# H3_CPU_01.net
KiCad netlist of a schematic drawn in Altium Designer
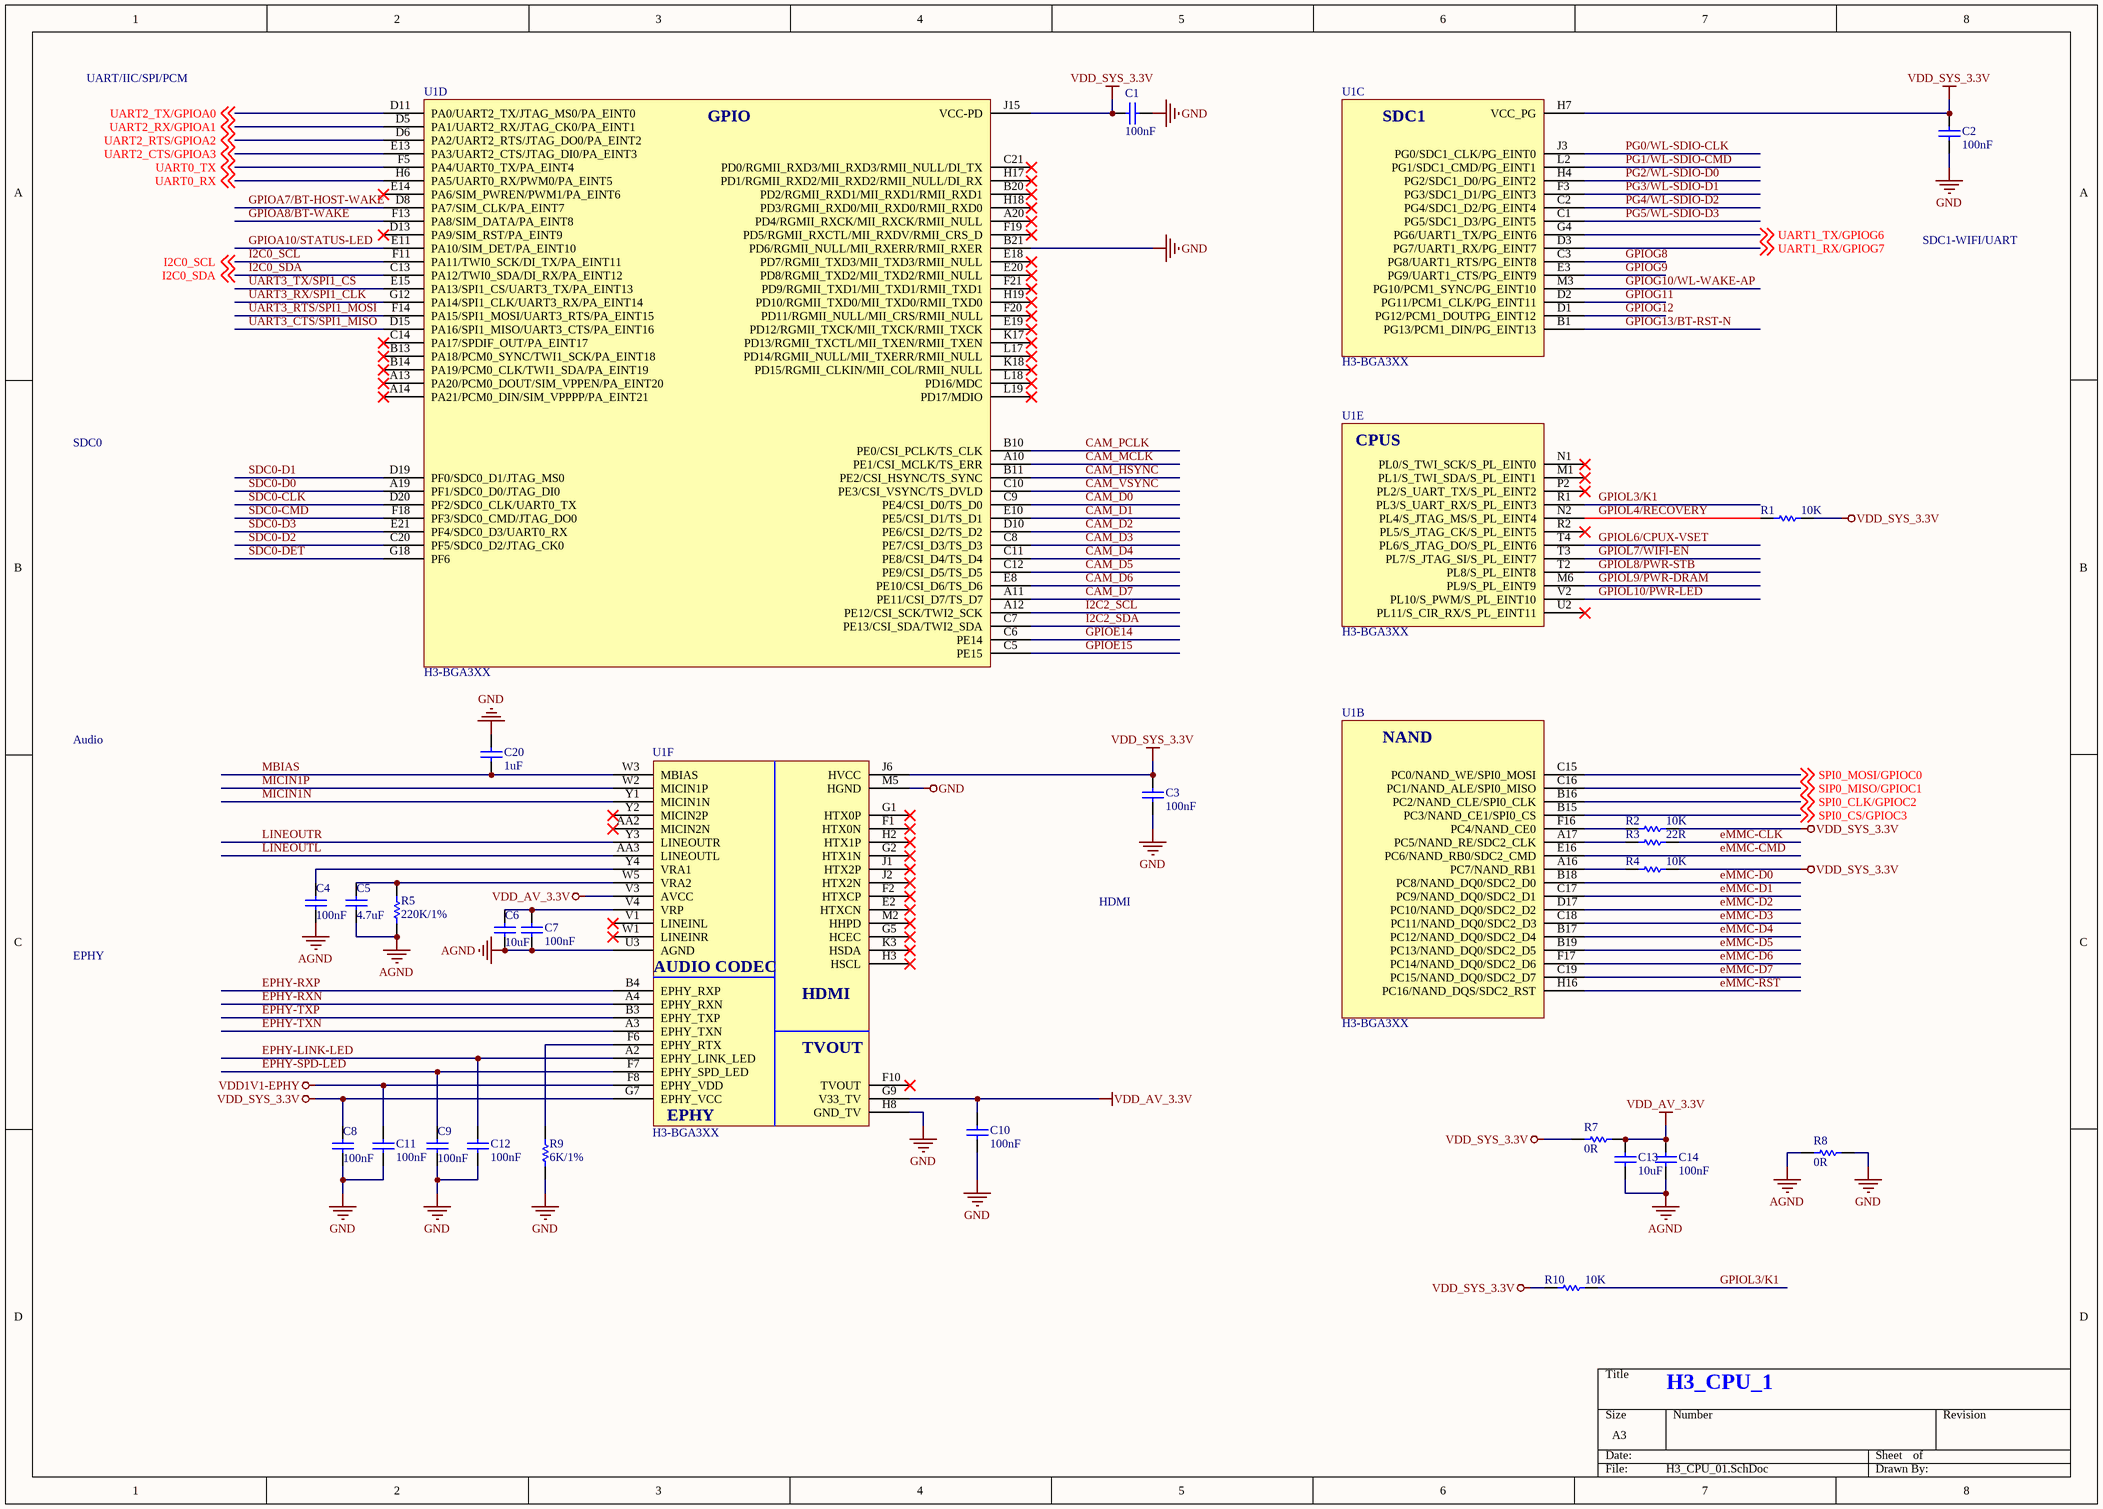
[diagram p0: H3_CPU_01.SchDoc]

(export (version "E")
  (design (tool "Eeschema 10.0.6"))
  (components
    (comp (ref "C1")
      (value "100nF")
      (footprint "H3_Core:C0402")
      (description "电容")
      (fields (field (name "PUBLISHER") "Altium Limited"))
      (libsource (lib "Devices") (part "C0402"))
    )
    (comp (ref "C2")
      (value "100nF")
      (footprint "H3_Core:C0402")
      (description "电容")
      (fields (field (name "PUBLISHER") "Altium Limited"))
      (libsource (lib "Devices") (part "C0402"))
    )
    (comp (ref "C3")
      (value "100nF")
      (footprint "H3_Core:C0402")
      (description "电容")
      (fields (field (name "PUBLISHER") "Altium Limited"))
      (libsource (lib "Devices") (part "C0402"))
    )
    (comp (ref "C4")
      (value "100nF")
      (footprint "H3_Core:C0402")
      (description "电容")
      (fields (field (name "PUBLISHER") "Altium Limited"))
      (libsource (lib "Devices") (part "C0402"))
    )
    (comp (ref "C5")
      (value "4.7uF")
      (footprint "H3_Core:C0402")
      (description "电容")
      (fields (field (name "PUBLISHER") "Altium Limited"))
      (libsource (lib "Devices") (part "C0402"))
    )
    (comp (ref "C6")
      (value "10uF")
      (footprint "H3_Core:C0603")
      (description "电容")
      (fields (field (name "PUBLISHER") "Altium Limited"))
      (libsource (lib "Devices") (part "C0603"))
    )
    (comp (ref "C7")
      (value "100nF")
      (footprint "H3_Core:C0402")
      (description "电容")
      (fields (field (name "PUBLISHER") "Altium Limited"))
      (libsource (lib "Devices") (part "C0402"))
    )
    (comp (ref "C8")
      (value "100nF")
      (footprint "H3_Core:C0402")
      (description "电容")
      (fields (field (name "PUBLISHER") "Altium Limited"))
      (libsource (lib "Devices") (part "C0402"))
    )
    (comp (ref "C9")
      (value "100nF")
      (footprint "H3_Core:C0402")
      (description "电容")
      (fields (field (name "PUBLISHER") "Altium Limited"))
      (libsource (lib "Devices") (part "C0402"))
    )
    (comp (ref "C10")
      (value "100nF")
      (footprint "H3_Core:C0402")
      (description "电容")
      (fields (field (name "PUBLISHER") "Altium Limited"))
      (libsource (lib "Devices") (part "C0402"))
    )
    (comp (ref "C11")
      (value "100nF")
      (footprint "H3_Core:C0402")
      (description "电容")
      (fields (field (name "PUBLISHER") "Altium Limited"))
      (libsource (lib "Devices") (part "C0402"))
    )
    (comp (ref "C12")
      (value "100nF")
      (footprint "H3_Core:C0402")
      (description "电容")
      (fields (field (name "PUBLISHER") "Altium Limited"))
      (libsource (lib "Devices") (part "C0402"))
    )
    (comp (ref "C13")
      (value "10uF")
      (footprint "H3_Core:C0603")
      (description "电容")
      (fields (field (name "PUBLISHER") "Altium Limited"))
      (libsource (lib "Devices") (part "C0603"))
    )
    (comp (ref "C14")
      (value "100nF")
      (footprint "H3_Core:C0402")
      (description "电容")
      (fields (field (name "PUBLISHER") "Altium Limited"))
      (libsource (lib "Devices") (part "C0402"))
    )
    (comp (ref "C20")
      (value "1uF")
      (footprint "H3_Core:C0402")
      (description "电容")
      (fields (field (name "PUBLISHER") "Altium Limited"))
      (libsource (lib "Devices") (part "C0402"))
    )
    (comp (ref "R1")
      (value "10K")
      (footprint "H3_Core:R0402")
      (description "电阻")
      (fields (field (name "PUBLISHER") "Altium Limited"))
      (libsource (lib "Devices") (part "RES0402"))
    )
    (comp (ref "R2")
      (value "10K")
      (footprint "H3_Core:R0402")
      (description "电阻")
      (fields (field (name "PUBLISHER") "Altium Limited"))
      (libsource (lib "Devices") (part "RES0402"))
    )
    (comp (ref "R3")
      (value "22R")
      (footprint "H3_Core:R0402")
      (description "电阻")
      (fields (field (name "PUBLISHER") "Altium Limited"))
      (libsource (lib "Devices") (part "RES0402"))
    )
    (comp (ref "R4")
      (value "10K")
      (footprint "H3_Core:R0402")
      (description "电阻")
      (fields (field (name "PUBLISHER") "Altium Limited"))
      (libsource (lib "Devices") (part "RES0402"))
    )
    (comp (ref "R5")
      (value "220K/1%")
      (footprint "H3_Core:R0402")
      (description "电阻")
      (fields (field (name "PUBLISHER") "Altium Limited"))
      (libsource (lib "Devices") (part "RES0402"))
    )
    (comp (ref "R7")
      (value "0R")
      (footprint "H3_Core:R0402")
      (description "电阻")
      (fields (field (name "PUBLISHER") "Altium Limited"))
      (libsource (lib "Devices") (part "RES0402"))
    )
    (comp (ref "R8")
      (value "0R")
      (footprint "H3_Core:R0402")
      (description "电阻")
      (fields (field (name "PUBLISHER") "Altium Limited"))
      (libsource (lib "Devices") (part "RES0402"))
    )
    (comp (ref "R9")
      (value "6K/1%")
      (footprint "H3_Core:R0402")
      (description "电阻")
      (fields (field (name "PUBLISHER") "Altium Limited"))
      (libsource (lib "Devices") (part "RES0402"))
    )
    (comp (ref "R10")
      (value "10K")
      (footprint "H3_Core:R0402")
      (description "电阻")
      (fields (field (name "PUBLISHER") "Altium Limited"))
      (libsource (lib "Devices") (part "RES0402"))
    )
    (comp (ref "U1") (value "H3-BGA3XX") (footprint "BGA-H3-347") (libsource (lib "IC") (part "H3-BGA3XX")))
  )
  (nets
    (net (code "1") (name "/CAM_D0") (class "Default")
      (node (ref "U1") (pin "C9") (pinfunction "PE4/CSI_D0/TS_D0_C9") (pintype "passive"))
    )
    (net (code "2") (name "/CAM_D1") (class "Default")
      (node (ref "U1") (pin "E10") (pinfunction "PE5/CSI_D1/TS_D1_E10") (pintype "passive"))
    )
    (net (code "3") (name "/CAM_D2") (class "Default")
      (node (ref "U1") (pin "D10") (pinfunction "PE6/CSI_D2/TS_D2_D10") (pintype "passive"))
    )
    (net (code "4") (name "/CAM_D3") (class "Default")
      (node (ref "U1") (pin "C8") (pinfunction "PE7/CSI_D3/TS_D3_C8") (pintype "passive"))
    )
    (net (code "5") (name "/CAM_D4") (class "Default")
      (node (ref "U1") (pin "C11") (pinfunction "PE8/CSI_D4/TS_D4_C11") (pintype "passive"))
    )
    (net (code "6") (name "/CAM_D5") (class "Default")
      (node (ref "U1") (pin "C12") (pinfunction "PE9/CSI_D5/TS_D5_C12") (pintype "passive"))
    )
    (net (code "7") (name "/CAM_D6") (class "Default")
      (node (ref "U1") (pin "E8") (pinfunction "PE10/CSI_D6/TS_D6_E8") (pintype "passive"))
    )
    (net (code "8") (name "/CAM_D7") (class "Default")
      (node (ref "U1") (pin "A11") (pinfunction "PE11/CSI_D7/TS_D7_A11") (pintype "passive"))
    )
    (net (code "9") (name "/CAM_HSYNC") (class "Default")
      (node (ref "U1") (pin "B11") (pinfunction "PE2/CSI_HSYNC/TS_SYNC_B11") (pintype "passive"))
    )
    (net (code "10") (name "/CAM_MCLK") (class "Default")
      (node (ref "U1") (pin "A10") (pinfunction "PE1/CSI_MCLK/TS_ERR_A10") (pintype "passive"))
    )
    (net (code "11") (name "/CAM_PCLK") (class "Default")
      (node (ref "U1") (pin "B10") (pinfunction "PE0/CSI_PCLK/TS_CLK_B10") (pintype "passive"))
    )
    (net (code "12") (name "/CAM_VSYNC") (class "Default")
      (node (ref "U1") (pin "C10") (pinfunction "PE3/CSI_VSYNC/TS_DVLD_C10") (pintype "passive"))
    )
    (net (code "13") (name "/EPHY-LINK-LED") (class "Default")
      (node (ref "C12") (pin "2") (pinfunction "2_2") (pintype "passive"))
      (node (ref "U1") (pin "A2") (pinfunction "EPHY_LINK_LED_A2") (pintype "passive"))
    )
    (net (code "14") (name "/EPHY-RXN") (class "Default")
      (node (ref "U1") (pin "A4") (pinfunction "EPHY_RXN_A4") (pintype "passive"))
    )
    (net (code "15") (name "/EPHY-RXP") (class "Default")
      (node (ref "U1") (pin "B4") (pinfunction "EPHY_RXP_B4") (pintype "passive"))
    )
    (net (code "16") (name "/EPHY-SPD-LED") (class "Default")
      (node (ref "C9") (pin "2") (pinfunction "2_2") (pintype "passive"))
      (node (ref "U1") (pin "F7") (pinfunction "EPHY_SPD_LED_F7") (pintype "passive"))
    )
    (net (code "17") (name "/EPHY-TXN") (class "Default")
      (node (ref "U1") (pin "A3") (pinfunction "EPHY_TXN_A3") (pintype "passive"))
    )
    (net (code "18") (name "/EPHY-TXP") (class "Default")
      (node (ref "U1") (pin "B3") (pinfunction "EPHY_TXP_B3") (pintype "passive"))
    )
    (net (code "19") (name "/GPIOA7{slash}BT-HOST-WAKE") (class "Default")
      (node (ref "U1") (pin "D8") (pinfunction "PA7/SIM_CLK/PA_EINT7_D8") (pintype "passive"))
    )
    (net (code "20") (name "/GPIOA8{slash}BT-WAKE") (class "Default")
      (node (ref "U1") (pin "F13") (pinfunction "PA8/SIM_DATA/PA_EINT8_F13") (pintype "passive"))
    )
    (net (code "21") (name "/GPIOA10{slash}STATUS-LED") (class "Default")
      (node (ref "U1") (pin "E11") (pinfunction "PA10/SIM_DET/PA_EINT10_E11") (pintype "passive"))
    )
    (net (code "22") (name "/GPIOE14") (class "Default")
      (node (ref "U1") (pin "C6") (pinfunction "PE14_C6") (pintype "passive"))
    )
    (net (code "23") (name "/GPIOE15") (class "Default")
      (node (ref "U1") (pin "C5") (pinfunction "PE15_C5") (pintype "passive"))
    )
    (net (code "24") (name "/GPIOG8") (class "Default")
      (node (ref "U1") (pin "C3") (pinfunction "PG8/UART1_RTS/PG_EINT8_C3") (pintype "passive"))
    )
    (net (code "25") (name "/GPIOG9") (class "Default")
      (node (ref "U1") (pin "E3") (pinfunction "PG9/UART1_CTS/PG_EINT9_E3") (pintype "passive"))
    )
    (net (code "26") (name "/GPIOG10{slash}WL-WAKE-AP") (class "Default")
      (node (ref "U1") (pin "M3") (pinfunction "PG10/PCM1_SYNC/PG_EINT10_M3") (pintype "passive"))
    )
    (net (code "27") (name "/GPIOG11") (class "Default")
      (node (ref "U1") (pin "D2") (pinfunction "PG11/PCM1_CLK/PG_EINT11_D2") (pintype "passive"))
    )
    (net (code "28") (name "/GPIOG12") (class "Default")
      (node (ref "U1") (pin "D1") (pinfunction "PG12/PCM1_DOUTPG_EINT12_D1") (pintype "passive"))
    )
    (net (code "29") (name "/GPIOG13{slash}BT-RST-N") (class "Default")
      (node (ref "U1") (pin "B1") (pinfunction "PG13/PCM1_DIN/PG_EINT13_B1") (pintype "passive"))
    )
    (net (code "30") (name "/GPIOL3{slash}K1") (class "Default")
      (node (ref "R10") (pin "1") (pinfunction "1_1") (pintype "passive"))
      (node (ref "U1") (pin "R1") (pinfunction "PL3/S_UART_RX/S_PL_EINT3_R1") (pintype "passive"))
    )
    (net (code "31") (name "/GPIOL4{slash}RECOVERY") (class "Default")
      (node (ref "R1") (pin "2") (pinfunction "2_2") (pintype "passive"))
      (node (ref "U1") (pin "N2") (pinfunction "PL4/S_JTAG_MS/S_PL_EINT4_N2") (pintype "passive"))
    )
    (net (code "32") (name "/GPIOL6{slash}CPUX-VSET") (class "Default")
      (node (ref "U1") (pin "T4") (pinfunction "PL6/S_JTAG_DO/S_PL_EINT6_T4") (pintype "passive"))
    )
    (net (code "33") (name "/GPIOL7{slash}WIFI-EN") (class "Default")
      (node (ref "U1") (pin "T3") (pinfunction "PL7/S_JTAG_SI/S_PL_EINT7_T3") (pintype "passive"))
    )
    (net (code "34") (name "/GPIOL8{slash}PWR-STB") (class "Default")
      (node (ref "U1") (pin "T2") (pinfunction "PL8/S_PL_EINT8_T2") (pintype "passive"))
    )
    (net (code "35") (name "/GPIOL9{slash}PWR-DRAM") (class "Default")
      (node (ref "U1") (pin "M6") (pinfunction "PL9/S_PL_EINT9_M6") (pintype "passive"))
    )
    (net (code "36") (name "/GPIOL10{slash}PWR-LED") (class "Default")
      (node (ref "U1") (pin "V2") (pinfunction "PL10/S_PWM/S_PL_EINT10_V2") (pintype "passive"))
    )
    (net (code "37") (name "/I2C2_SCL") (class "Default")
      (node (ref "U1") (pin "A12") (pinfunction "PE12/CSI_SCK/TWI2_SCK_A12") (pintype "passive"))
    )
    (net (code "38") (name "/I2C2_SDA") (class "Default")
      (node (ref "U1") (pin "C7") (pinfunction "PE13/CSI_SDA/TWI2_SDA_C7") (pintype "passive"))
    )
    (net (code "39") (name "/LINEOUTL") (class "Default")
      (node (ref "U1") (pin "AA3") (pinfunction "LINEOUTL_AA3") (pintype "passive"))
    )
    (net (code "40") (name "/LINEOUTR") (class "Default")
      (node (ref "U1") (pin "Y3") (pinfunction "LINEOUTR_Y3") (pintype "passive"))
    )
    (net (code "41") (name "/MBIAS") (class "Default")
      (node (ref "C20") (pin "1") (pinfunction "1_1") (pintype "passive"))
      (node (ref "U1") (pin "W3") (pinfunction "MBIAS_W3") (pintype "passive"))
    )
    (net (code "42") (name "/MICIN1N") (class "Default")
      (node (ref "U1") (pin "Y1") (pinfunction "MICIN1N_Y1") (pintype "passive"))
    )
    (net (code "43") (name "/MICIN1P") (class "Default")
      (node (ref "U1") (pin "W2") (pinfunction "MICIN1P_W2") (pintype "passive"))
    )
    (net (code "44") (name "/PG0{slash}WL-SDIO-CLK") (class "Default")
      (node (ref "U1") (pin "J3") (pinfunction "PG0/SDC1_CLK/PG_EINT0_J3") (pintype "passive"))
    )
    (net (code "45") (name "/PG1{slash}WL-SDIO-CMD") (class "Default")
      (node (ref "U1") (pin "L2") (pinfunction "PG1/SDC1_CMD/PG_EINT1_L2") (pintype "passive"))
    )
    (net (code "46") (name "/PG2{slash}WL-SDIO-D0") (class "Default")
      (node (ref "U1") (pin "H4") (pinfunction "PG2/SDC1_D0/PG_EINT2_H4") (pintype "passive"))
    )
    (net (code "47") (name "/PG3{slash}WL-SDIO-D1") (class "Default")
      (node (ref "U1") (pin "F3") (pinfunction "PG3/SDC1_D1/PG_EINT3_F3") (pintype "passive"))
    )
    (net (code "48") (name "/PG4{slash}WL-SDIO-D2") (class "Default")
      (node (ref "U1") (pin "C2") (pinfunction "PG4/SDC1_D2/PG_EINT4_C2") (pintype "passive"))
    )
    (net (code "49") (name "/PG5{slash}WL-SDIO-D3") (class "Default")
      (node (ref "U1") (pin "C1") (pinfunction "PG5/SDC1_D3/PG_EINT5_C1") (pintype "passive"))
    )
    (net (code "50") (name "/SDC0-CLK") (class "Default")
      (node (ref "U1") (pin "D20") (pinfunction "PF2/SDC0_CLK/UART0_TX_D20") (pintype "passive"))
    )
    (net (code "51") (name "/SDC0-CMD") (class "Default")
      (node (ref "U1") (pin "F18") (pinfunction "PF3/SDC0_CMD/JTAG_DO0_F18") (pintype "passive"))
    )
    (net (code "52") (name "/SDC0-D0") (class "Default")
      (node (ref "U1") (pin "A19") (pinfunction "PF1/SDC0_D0/JTAG_DI0_A19") (pintype "passive"))
    )
    (net (code "53") (name "/SDC0-D1") (class "Default")
      (node (ref "U1") (pin "D19") (pinfunction "PF0/SDC0_D1/JTAG_MS0_D19") (pintype "passive"))
    )
    (net (code "54") (name "/SDC0-D2") (class "Default")
      (node (ref "U1") (pin "C20") (pinfunction "PF5/SDC0_D2/JTAG_CK0_C20") (pintype "passive"))
    )
    (net (code "55") (name "/SDC0-D3") (class "Default")
      (node (ref "U1") (pin "E21") (pinfunction "PF4/SDC0_D3/UART0_RX_E21") (pintype "passive"))
    )
    (net (code "56") (name "/SDC0-DET") (class "Default")
      (node (ref "U1") (pin "G18") (pinfunction "PF6_G18") (pintype "passive"))
    )
    (net (code "57") (name "/UART3_CTS{slash}SPI1_MISO") (class "Default")
      (node (ref "U1") (pin "D15") (pinfunction "PA16/SPI1_MISO/UART3_CTS/PA_EINT16_D15") (pintype "passive"))
    )
    (net (code "58") (name "/UART3_RTS{slash}SPI1_MOSI") (class "Default")
      (node (ref "U1") (pin "F14") (pinfunction "PA15/SPI1_MOSI/UART3_RTS/PA_EINT15_F14") (pintype "passive"))
    )
    (net (code "59") (name "/UART3_RX{slash}SPI1_CLK") (class "Default")
      (node (ref "U1") (pin "G12") (pinfunction "PA14/SPI1_CLK/UART3_RX/PA_EINT14_G12") (pintype "passive"))
    )
    (net (code "60") (name "/UART3_TX{slash}SPI1_CS") (class "Default")
      (node (ref "U1") (pin "E15") (pinfunction "PA13/SPI1_CS/UART3_TX/PA_EINT13_E15") (pintype "passive"))
    )
    (net (code "61") (name "/eMMC-CLK") (class "Default")
      (node (ref "R3") (pin "1") (pinfunction "1_1") (pintype "passive"))
    )
    (net (code "62") (name "/eMMC-CMD") (class "Default")
      (node (ref "U1") (pin "E16") (pinfunction "PC6/NAND_RB0/SDC2_CMD_E16") (pintype "passive"))
    )
    (net (code "63") (name "/eMMC-D0") (class "Default")
      (node (ref "U1") (pin "B18") (pinfunction "PC8/NAND_DQ0/SDC2_D0_B18") (pintype "passive"))
    )
    (net (code "64") (name "/eMMC-D1") (class "Default")
      (node (ref "U1") (pin "C17") (pinfunction "PC9/NAND_DQ0/SDC2_D1_C17") (pintype "passive"))
    )
    (net (code "65") (name "/eMMC-D2") (class "Default")
      (node (ref "U1") (pin "D17") (pinfunction "PC10/NAND_DQ0/SDC2_D2_D17") (pintype "passive"))
    )
    (net (code "66") (name "/eMMC-D3") (class "Default")
      (node (ref "U1") (pin "C18") (pinfunction "PC11/NAND_DQ0/SDC2_D3_C18") (pintype "passive"))
    )
    (net (code "67") (name "/eMMC-D4") (class "Default")
      (node (ref "U1") (pin "B17") (pinfunction "PC12/NAND_DQ0/SDC2_D4_B17") (pintype "passive"))
    )
    (net (code "68") (name "/eMMC-D5") (class "Default")
      (node (ref "U1") (pin "B19") (pinfunction "PC13/NAND_DQ0/SDC2_D5_B19") (pintype "passive"))
    )
    (net (code "69") (name "/eMMC-D6") (class "Default")
      (node (ref "U1") (pin "F17") (pinfunction "PC14/NAND_DQ0/SDC2_D6_F17") (pintype "passive"))
    )
    (net (code "70") (name "/eMMC-D7") (class "Default")
      (node (ref "U1") (pin "C19") (pinfunction "PC15/NAND_DQ0/SDC2_D7_C19") (pintype "passive"))
    )
    (net (code "71") (name "/eMMC-RST") (class "Default")
      (node (ref "U1") (pin "H16") (pinfunction "PC16/NAND_DQS/SDC2_RST_H16") (pintype "passive"))
    )
    (net (code "72") (name "AGND") (class "Default")
      (node (ref "C13") (pin "1") (pinfunction "1_1") (pintype "passive"))
      (node (ref "C14") (pin "1") (pinfunction "1_1") (pintype "passive"))
      (node (ref "C4") (pin "1") (pinfunction "1_1") (pintype "passive"))
      (node (ref "C5") (pin "1") (pinfunction "1_1") (pintype "passive"))
      (node (ref "C6") (pin "1") (pinfunction "1_1") (pintype "passive"))
      (node (ref "C7") (pin "1") (pinfunction "1_1") (pintype "passive"))
      (node (ref "R5") (pin "1") (pinfunction "1_1") (pintype "passive"))
      (node (ref "R8") (pin "1") (pinfunction "1_1") (pintype "passive"))
      (node (ref "U1") (pin "U3") (pinfunction "AGND_U3") (pintype "passive"))
    )
    (net (code "73") (name "GND") (class "Default")
      (node (ref "C1") (pin "1") (pinfunction "1_1") (pintype "passive"))
      (node (ref "C10") (pin "1") (pinfunction "1_1") (pintype "passive"))
      (node (ref "C11") (pin "1") (pinfunction "1_1") (pintype "passive"))
      (node (ref "C12") (pin "1") (pinfunction "1_1") (pintype "passive"))
      (node (ref "C2") (pin "1") (pinfunction "1_1") (pintype "passive"))
      (node (ref "C20") (pin "2") (pinfunction "2_2") (pintype "passive"))
      (node (ref "C3") (pin "1") (pinfunction "1_1") (pintype "passive"))
      (node (ref "C8") (pin "1") (pinfunction "1_1") (pintype "passive"))
      (node (ref "C9") (pin "1") (pinfunction "1_1") (pintype "passive"))
      (node (ref "R8") (pin "2") (pinfunction "2_2") (pintype "passive"))
      (node (ref "R9") (pin "1") (pinfunction "1_1") (pintype "passive"))
      (node (ref "U1") (pin "B21") (pinfunction "PD6/RGMII_NULL/MII_RXERR/RMII_RXER_B21") (pintype "passive"))
      (node (ref "U1") (pin "H8") (pinfunction "GND_TV_H8") (pintype "passive"))
      (node (ref "U1") (pin "M5") (pinfunction "HGND_M5") (pintype "passive"))
    )
    (net (code "74") (name "I2C0_SCL") (class "Default")
      (node (ref "U1") (pin "F11") (pinfunction "PA11/TWI0_SCK/DI_TX/PA_EINT11_F11") (pintype "passive"))
    )
    (net (code "75") (name "I2C0_SDA") (class "Default")
      (node (ref "U1") (pin "C13") (pinfunction "PA12/TWI0_SDA/DI_RX/PA_EINT12_C13") (pintype "passive"))
    )
    (net (code "76") (name "Net-(U1B-PC4{slash}NAND_CE0)") (class "Default")
      (node (ref "R2") (pin "2") (pinfunction "2_2") (pintype "passive"))
      (node (ref "U1") (pin "F16") (pinfunction "PC4/NAND_CE0_F16") (pintype "passive"))
    )
    (net (code "77") (name "Net-(U1B-PC5{slash}NAND_RE{slash}SDC2_CLK)") (class "Default")
      (node (ref "R3") (pin "2") (pinfunction "2_2") (pintype "passive"))
      (node (ref "U1") (pin "A17") (pinfunction "PC5/NAND_RE/SDC2_CLK_A17") (pintype "passive"))
    )
    (net (code "78") (name "Net-(U1B-PC7{slash}NAND_RB1)") (class "Default")
      (node (ref "R4") (pin "2") (pinfunction "2_2") (pintype "passive"))
      (node (ref "U1") (pin "A16") (pinfunction "PC7/NAND_RB1_A16") (pintype "passive"))
    )
    (net (code "79") (name "Net-(U1F-EPHY_RTX)") (class "Default")
      (node (ref "R9") (pin "2") (pinfunction "2_2") (pintype "passive"))
      (node (ref "U1") (pin "F6") (pinfunction "EPHY_RTX_F6") (pintype "passive"))
    )
    (net (code "80") (name "Net-(U1F-VRA1)") (class "Default")
      (node (ref "C4") (pin "2") (pinfunction "2_2") (pintype "passive"))
      (node (ref "U1") (pin "Y4") (pinfunction "VRA1_Y4") (pintype "passive"))
    )
    (net (code "81") (name "Net-(U1F-VRA2)") (class "Default")
      (node (ref "C5") (pin "2") (pinfunction "2_2") (pintype "passive"))
      (node (ref "R5") (pin "2") (pinfunction "2_2") (pintype "passive"))
      (node (ref "U1") (pin "W5") (pinfunction "VRA2_W5") (pintype "passive"))
    )
    (net (code "82") (name "Net-(U1F-VRP)") (class "Default")
      (node (ref "C6") (pin "2") (pinfunction "2_2") (pintype "passive"))
      (node (ref "C7") (pin "2") (pinfunction "2_2") (pintype "passive"))
      (node (ref "U1") (pin "V4") (pinfunction "VRP_V4") (pintype "passive"))
    )
    (net (code "83") (name "SIP0_MISO{slash}GPIOC1") (class "Default")
      (node (ref "U1") (pin "C16") (pinfunction "PC1/NAND_ALE/SPI0_MISO_C16") (pintype "passive"))
    )
    (net (code "84") (name "SPI0_CLK{slash}GPIOC2") (class "Default")
      (node (ref "U1") (pin "B16") (pinfunction "PC2/NAND_CLE/SPI0_CLK_B16") (pintype "passive"))
    )
    (net (code "85") (name "SPI0_CS{slash}GPIOC3") (class "Default")
      (node (ref "U1") (pin "B15") (pinfunction "PC3/NAND_CE1/SPI0_CS_B15") (pintype "passive"))
    )
    (net (code "86") (name "SPI0_MOSI{slash}GPIOC0") (class "Default")
      (node (ref "U1") (pin "C15") (pinfunction "PC0/NAND_WE/SPI0_MOSI_C15") (pintype "passive"))
    )
    (net (code "87") (name "UART0_RX") (class "Default")
      (node (ref "U1") (pin "H6") (pinfunction "PA5/UART0_RX/PWM0/PA_EINT5_H6") (pintype "passive"))
    )
    (net (code "88") (name "UART0_TX") (class "Default")
      (node (ref "U1") (pin "F5") (pinfunction "PA4/UART0_TX/PA_EINT4_F5") (pintype "passive"))
    )
    (net (code "89") (name "UART1_RX{slash}GPIOG7") (class "Default")
      (node (ref "U1") (pin "D3") (pinfunction "PG7/UART1_RX/PG_EINT7_D3") (pintype "passive"))
    )
    (net (code "90") (name "UART1_TX{slash}GPIOG6") (class "Default")
      (node (ref "U1") (pin "G4") (pinfunction "PG6/UART1_TX/PG_EINT6_G4") (pintype "passive"))
    )
    (net (code "91") (name "UART2_CTS{slash}GPIOA3") (class "Default")
      (node (ref "U1") (pin "E13") (pinfunction "PA3/UART2_CTS/JTAG_DI0/PA_EINT3_E13") (pintype "passive"))
    )
    (net (code "92") (name "UART2_RTS{slash}GPIOA2") (class "Default")
      (node (ref "U1") (pin "D6") (pinfunction "PA2/UART2_RTS/JTAG_DO0/PA_EINT2_D6") (pintype "passive"))
    )
    (net (code "93") (name "UART2_RX{slash}GPIOA1") (class "Default")
      (node (ref "U1") (pin "D5") (pinfunction "PA1/UART2_RX/JTAG_CK0/PA_EINT1_D5") (pintype "passive"))
    )
    (net (code "94") (name "UART2_TX{slash}GPIOA0") (class "Default")
      (node (ref "U1") (pin "D11") (pinfunction "PA0/UART2_TX/JTAG_MS0/PA_EINT0_D11") (pintype "passive"))
    )
    (net (code "95") (name "VDD1V1-EPHY") (class "Default")
      (node (ref "C11") (pin "2") (pinfunction "2_2") (pintype "passive"))
      (node (ref "U1") (pin "F8") (pinfunction "EPHY_VDD_F8") (pintype "passive"))
    )
    (net (code "96") (name "VDD_AV_3.3V") (class "Default")
      (node (ref "C10") (pin "2") (pinfunction "2_2") (pintype "passive"))
      (node (ref "C13") (pin "2") (pinfunction "2_2") (pintype "passive"))
      (node (ref "C14") (pin "2") (pinfunction "2_2") (pintype "passive"))
      (node (ref "R7") (pin "2") (pinfunction "2_2") (pintype "passive"))
      (node (ref "U1") (pin "G9") (pinfunction "V33_TV_G9") (pintype "passive"))
      (node (ref "U1") (pin "V3") (pinfunction "AVCC_V3") (pintype "passive"))
    )
    (net (code "97") (name "VDD_SYS_3.3V") (class "Default")
      (node (ref "C1") (pin "2") (pinfunction "2_2") (pintype "passive"))
      (node (ref "C2") (pin "2") (pinfunction "2_2") (pintype "passive"))
      (node (ref "C3") (pin "2") (pinfunction "2_2") (pintype "passive"))
      (node (ref "C8") (pin "2") (pinfunction "2_2") (pintype "passive"))
      (node (ref "R1") (pin "1") (pinfunction "1_1") (pintype "passive"))
      (node (ref "R10") (pin "2") (pinfunction "2_2") (pintype "passive"))
      (node (ref "R2") (pin "1") (pinfunction "1_1") (pintype "passive"))
      (node (ref "R4") (pin "1") (pinfunction "1_1") (pintype "passive"))
      (node (ref "R7") (pin "1") (pinfunction "1_1") (pintype "passive"))
      (node (ref "U1") (pin "G7") (pinfunction "EPHY_VCC_G7") (pintype "passive"))
      (node (ref "U1") (pin "H7") (pinfunction "VCC_PG_H7") (pintype "passive"))
      (node (ref "U1") (pin "J15") (pinfunction "VCC-PD_J15") (pintype "passive"))
      (node (ref "U1") (pin "J6") (pinfunction "HVCC_J6") (pintype "passive"))
    )
    (net (code "98") (name "unconnected-(U1D-PA6{slash}SIM_PWREN{slash}PWM1{slash}PA_EINT6-PadE14)") (class "Default")
      (node (ref "U1") (pin "E14") (pinfunction "PA6/SIM_PWREN/PWM1/PA_EINT6_E14") (pintype "passive+no_connect"))
    )
    (net (code "99") (name "unconnected-(U1D-PA9{slash}SIM_RST{slash}PA_EINT9-PadD13)") (class "Default")
      (node (ref "U1") (pin "D13") (pinfunction "PA9/SIM_RST/PA_EINT9_D13") (pintype "passive+no_connect"))
    )
    (net (code "100") (name "unconnected-(U1D-PA17{slash}SPDIF_OUT{slash}PA_EINT17-PadC14)") (class "Default")
      (node (ref "U1") (pin "C14") (pinfunction "PA17/SPDIF_OUT/PA_EINT17_C14") (pintype "passive+no_connect"))
    )
    (net (code "101") (name "unconnected-(U1D-PA18{slash}PCM0_SYNC{slash}TWI1_SCK{slash}PA_EINT18-PadB13)") (class "Default")
      (node (ref "U1") (pin "B13") (pinfunction "PA18/PCM0_SYNC/TWI1_SCK/PA_EINT18_B13") (pintype "passive+no_connect"))
    )
    (net (code "102") (name "unconnected-(U1D-PA19{slash}PCM0_CLK{slash}TWI1_SDA{slash}PA_EINT19-PadB14)") (class "Default")
      (node (ref "U1") (pin "B14") (pinfunction "PA19/PCM0_CLK/TWI1_SDA/PA_EINT19_B14") (pintype "passive+no_connect"))
    )
    (net (code "103") (name "unconnected-(U1D-PA20{slash}PCM0_DOUT{slash}SIM_VPPEN{slash}PA_EINT20-PadA13)") (class "Default")
      (node (ref "U1") (pin "A13") (pinfunction "PA20/PCM0_DOUT/SIM_VPPEN/PA_EINT20_A13") (pintype "passive+no_connect"))
    )
    (net (code "104") (name "unconnected-(U1D-PA21{slash}PCM0_DIN{slash}SIM_VPPPP{slash}PA_EINT21-PadA14)") (class "Default")
      (node (ref "U1") (pin "A14") (pinfunction "PA21/PCM0_DIN/SIM_VPPPP/PA_EINT21_A14") (pintype "passive+no_connect"))
    )
    (net (code "105") (name "unconnected-(U1D-PD0{slash}RGMII_RXD3{slash}MII_RXD3{slash}RMII_NULL{slash}DI_TX-PadC21)") (class "Default")
      (node (ref "U1") (pin "C21") (pinfunction "PD0/RGMII_RXD3/MII_RXD3/RMII_NULL/DI_TX_C21") (pintype "passive+no_connect"))
    )
    (net (code "106") (name "unconnected-(U1D-PD1{slash}RGMII_RXD2{slash}MII_RXD2{slash}RMII_NULL{slash}DI_RX-PadH17)") (class "Default")
      (node (ref "U1") (pin "H17") (pinfunction "PD1/RGMII_RXD2/MII_RXD2/RMII_NULL/DI_RX_H17") (pintype "passive+no_connect"))
    )
    (net (code "107") (name "unconnected-(U1D-PD2{slash}RGMII_RXD1{slash}MII_RXD1{slash}RMII_RXD1-PadB20)") (class "Default")
      (node (ref "U1") (pin "B20") (pinfunction "PD2/RGMII_RXD1/MII_RXD1/RMII_RXD1_B20") (pintype "passive+no_connect"))
    )
    (net (code "108") (name "unconnected-(U1D-PD3{slash}RGMII_RXD0{slash}MII_RXD0{slash}RMII_RXD0-PadH18)") (class "Default")
      (node (ref "U1") (pin "H18") (pinfunction "PD3/RGMII_RXD0/MII_RXD0/RMII_RXD0_H18") (pintype "passive+no_connect"))
    )
    (net (code "109") (name "unconnected-(U1D-PD4{slash}RGMII_RXCK{slash}MII_RXCK{slash}RMII_NULL-PadA20)") (class "Default")
      (node (ref "U1") (pin "A20") (pinfunction "PD4/RGMII_RXCK/MII_RXCK/RMII_NULL_A20") (pintype "passive+no_connect"))
    )
    (net (code "110") (name "unconnected-(U1D-PD5{slash}RGMII_RXCTL{slash}MII_RXDV{slash}RMII_CRS_D-PadF19)") (class "Default")
      (node (ref "U1") (pin "F19") (pinfunction "PD5/RGMII_RXCTL/MII_RXDV/RMII_CRS_D_F19") (pintype "passive+no_connect"))
    )
    (net (code "111") (name "unconnected-(U1D-PD7{slash}RGMII_TXD3{slash}MII_TXD3{slash}RMII_NULL-PadE18)") (class "Default")
      (node (ref "U1") (pin "E18") (pinfunction "PD7/RGMII_TXD3/MII_TXD3/RMII_NULL_E18") (pintype "passive+no_connect"))
    )
    (net (code "112") (name "unconnected-(U1D-PD8{slash}RGMII_TXD2{slash}MII_TXD2{slash}RMII_NULL-PadE20)") (class "Default")
      (node (ref "U1") (pin "E20") (pinfunction "PD8/RGMII_TXD2/MII_TXD2/RMII_NULL_E20") (pintype "passive+no_connect"))
    )
    (net (code "113") (name "unconnected-(U1D-PD9{slash}RGMII_TXD1{slash}MII_TXD1{slash}RMII_TXD1-PadF21)") (class "Default")
      (node (ref "U1") (pin "F21") (pinfunction "PD9/RGMII_TXD1/MII_TXD1/RMII_TXD1_F21") (pintype "passive+no_connect"))
    )
    (net (code "114") (name "unconnected-(U1D-PD10{slash}RGMII_TXD0{slash}MII_TXD0{slash}RMII_TXD0-PadH19)") (class "Default")
      (node (ref "U1") (pin "H19") (pinfunction "PD10/RGMII_TXD0/MII_TXD0/RMII_TXD0_H19") (pintype "passive+no_connect"))
    )
    (net (code "115") (name "unconnected-(U1D-PD11{slash}RGMII_NULL{slash}MII_CRS{slash}RMII_NULL-PadF20)") (class "Default")
      (node (ref "U1") (pin "F20") (pinfunction "PD11/RGMII_NULL/MII_CRS/RMII_NULL_F20") (pintype "passive+no_connect"))
    )
    (net (code "116") (name "unconnected-(U1D-PD12{slash}RGMII_TXCK{slash}MII_TXCK{slash}RMII_TXCK-PadE19)") (class "Default")
      (node (ref "U1") (pin "E19") (pinfunction "PD12/RGMII_TXCK/MII_TXCK/RMII_TXCK_E19") (pintype "passive+no_connect"))
    )
    (net (code "117") (name "unconnected-(U1D-PD13{slash}RGMII_TXCTL{slash}MII_TXEN{slash}RMII_TXEN-PadK17)") (class "Default")
      (node (ref "U1") (pin "K17") (pinfunction "PD13/RGMII_TXCTL/MII_TXEN/RMII_TXEN_K17") (pintype "passive+no_connect"))
    )
    (net (code "118") (name "unconnected-(U1D-PD14{slash}RGMII_NULL{slash}MII_TXERR{slash}RMII_NULL-PadL17)") (class "Default")
      (node (ref "U1") (pin "L17") (pinfunction "PD14/RGMII_NULL/MII_TXERR/RMII_NULL_L17") (pintype "passive+no_connect"))
    )
    (net (code "119") (name "unconnected-(U1D-PD15{slash}RGMII_CLKIN{slash}MII_COL{slash}RMII_NULL-PadK18)") (class "Default")
      (node (ref "U1") (pin "K18") (pinfunction "PD15/RGMII_CLKIN/MII_COL/RMII_NULL_K18") (pintype "passive+no_connect"))
    )
    (net (code "120") (name "unconnected-(U1D-PD16{slash}MDC-PadL18)") (class "Default")
      (node (ref "U1") (pin "L18") (pinfunction "PD16/MDC_L18") (pintype "passive+no_connect"))
    )
    (net (code "121") (name "unconnected-(U1D-PD17{slash}MDIO-PadL19)") (class "Default")
      (node (ref "U1") (pin "L19") (pinfunction "PD17/MDIO_L19") (pintype "passive+no_connect"))
    )
    (net (code "122") (name "unconnected-(U1E-PL0{slash}S_TWI_SCK{slash}S_PL_EINT0-PadN1)") (class "Default")
      (node (ref "U1") (pin "N1") (pinfunction "PL0/S_TWI_SCK/S_PL_EINT0_N1") (pintype "passive+no_connect"))
    )
    (net (code "123") (name "unconnected-(U1E-PL1{slash}S_TWI_SDA{slash}S_PL_EINT1-PadM1)") (class "Default")
      (node (ref "U1") (pin "M1") (pinfunction "PL1/S_TWI_SDA/S_PL_EINT1_M1") (pintype "passive+no_connect"))
    )
    (net (code "124") (name "unconnected-(U1E-PL2{slash}S_UART_TX{slash}S_PL_EINT2-PadP2)") (class "Default")
      (node (ref "U1") (pin "P2") (pinfunction "PL2/S_UART_TX/S_PL_EINT2_P2") (pintype "passive+no_connect"))
    )
    (net (code "125") (name "unconnected-(U1E-PL5{slash}S_JTAG_CK{slash}S_PL_EINT5-PadR2)") (class "Default")
      (node (ref "U1") (pin "R2") (pinfunction "PL5/S_JTAG_CK/S_PL_EINT5_R2") (pintype "passive+no_connect"))
    )
    (net (code "126") (name "unconnected-(U1E-PL11{slash}S_CIR_RX{slash}S_PL_EINT11-PadU2)") (class "Default")
      (node (ref "U1") (pin "U2") (pinfunction "PL11/S_CIR_RX/S_PL_EINT11_U2") (pintype "passive+no_connect"))
    )
    (net (code "127") (name "unconnected-(U1F-HCEC-PadG5)") (class "Default")
      (node (ref "U1") (pin "G5") (pinfunction "HCEC_G5") (pintype "passive+no_connect"))
    )
    (net (code "128") (name "unconnected-(U1F-HHPD-PadM2)") (class "Default")
      (node (ref "U1") (pin "M2") (pinfunction "HHPD_M2") (pintype "passive+no_connect"))
    )
    (net (code "129") (name "unconnected-(U1F-HSCL-PadH3)") (class "Default")
      (node (ref "U1") (pin "H3") (pinfunction "HSCL_H3") (pintype "passive+no_connect"))
    )
    (net (code "130") (name "unconnected-(U1F-HSDA-PadK3)") (class "Default")
      (node (ref "U1") (pin "K3") (pinfunction "HSDA_K3") (pintype "passive+no_connect"))
    )
    (net (code "131") (name "unconnected-(U1F-HTX0N-PadF1)") (class "Default")
      (node (ref "U1") (pin "F1") (pinfunction "HTX0N_F1") (pintype "passive+no_connect"))
    )
    (net (code "132") (name "unconnected-(U1F-HTX0P-PadG1)") (class "Default")
      (node (ref "U1") (pin "G1") (pinfunction "HTX0P_G1") (pintype "passive+no_connect"))
    )
    (net (code "133") (name "unconnected-(U1F-HTX1N-PadG2)") (class "Default")
      (node (ref "U1") (pin "G2") (pinfunction "HTX1N_G2") (pintype "passive+no_connect"))
    )
    (net (code "134") (name "unconnected-(U1F-HTX1P-PadH2)") (class "Default")
      (node (ref "U1") (pin "H2") (pinfunction "HTX1P_H2") (pintype "passive+no_connect"))
    )
    (net (code "135") (name "unconnected-(U1F-HTX2N-PadJ2)") (class "Default")
      (node (ref "U1") (pin "J2") (pinfunction "HTX2N_J2") (pintype "passive+no_connect"))
    )
    (net (code "136") (name "unconnected-(U1F-HTX2P-PadJ1)") (class "Default")
      (node (ref "U1") (pin "J1") (pinfunction "HTX2P_J1") (pintype "passive+no_connect"))
    )
    (net (code "137") (name "unconnected-(U1F-HTXCN-PadE2)") (class "Default")
      (node (ref "U1") (pin "E2") (pinfunction "HTXCN_E2") (pintype "passive+no_connect"))
    )
    (net (code "138") (name "unconnected-(U1F-HTXCP-PadF2)") (class "Default")
      (node (ref "U1") (pin "F2") (pinfunction "HTXCP_F2") (pintype "passive+no_connect"))
    )
    (net (code "139") (name "unconnected-(U1F-LINEINL-PadV1)") (class "Default")
      (node (ref "U1") (pin "V1") (pinfunction "LINEINL_V1") (pintype "passive+no_connect"))
    )
    (net (code "140") (name "unconnected-(U1F-LINEINR-PadW1)") (class "Default")
      (node (ref "U1") (pin "W1") (pinfunction "LINEINR_W1") (pintype "passive+no_connect"))
    )
    (net (code "141") (name "unconnected-(U1F-MICIN2N-PadAA2)") (class "Default")
      (node (ref "U1") (pin "AA2") (pinfunction "MICIN2N_AA2") (pintype "passive+no_connect"))
    )
    (net (code "142") (name "unconnected-(U1F-MICIN2P-PadY2)") (class "Default")
      (node (ref "U1") (pin "Y2") (pinfunction "MICIN2P_Y2") (pintype "passive+no_connect"))
    )
    (net (code "143") (name "unconnected-(U1F-TVOUT-PadF10)") (class "Default")
      (node (ref "U1") (pin "F10") (pinfunction "TVOUT_F10") (pintype "passive+no_connect"))
    )
  )
)
